# thermo_test.net
KiCad netlist of a schematic drawn in EAGLE
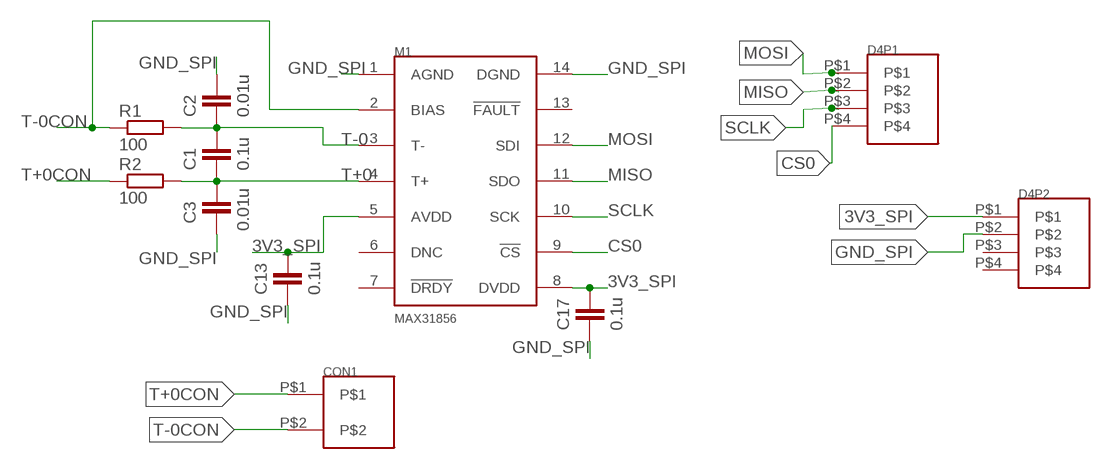
[diagram p0: schematic, sheet 1]

(export (version "E")
  (design (tool "Eeschema 10.0.6"))
  (components
    (comp (ref "C1")
      (value "0.1u")
      (footprint "eagle-import:C0603")
      (libsource (lib "eagle-import") (part "C-EUC0603"))
    )
    (comp (ref "C2")
      (value "0.01u")
      (footprint "eagle-import:C0603")
      (libsource (lib "eagle-import") (part "C-EUC0603"))
    )
    (comp (ref "C3")
      (value "0.01u")
      (footprint "eagle-import:C0603")
      (libsource (lib "eagle-import") (part "C-EUC0603"))
    )
    (comp (ref "C13")
      (value "0.1u")
      (footprint "eagle-import:C0603")
      (libsource (lib "eagle-import") (part "C-EUC0603"))
    )
    (comp (ref "C17")
      (value "0.1u")
      (footprint "eagle-import:C0603")
      (libsource (lib "eagle-import") (part "C-EUC0603"))
    )
    (comp (ref "CON1")
      (value "893-1332")
      (footprint "eagle-import:893-1332")
      (libsource (lib "eagle-import") (part "893-1332"))
    )
    (comp (ref "D4P1")
      (value "DF1E-4P")
      (footprint "eagle-import:DF1E-4P")
      (libsource (lib "eagle-import") (part "DF1E-4P"))
    )
    (comp (ref "D4P2")
      (value "DF1E-4P")
      (footprint "eagle-import:DF1E-4P")
      (libsource (lib "eagle-import") (part "DF1E-4P"))
    )
    (comp (ref "M1")
      (value "MAX31856")
      (footprint "eagle-import:TSSOP14")
      (libsource (lib "eagle-import") (part "MAX31856"))
    )
    (comp (ref "R1")
      (value "100")
      (footprint "eagle-import:R0603")
      (libsource (lib "eagle-import") (part "R-EU_R0603"))
    )
    (comp (ref "R2")
      (value "100")
      (footprint "eagle-import:R0603")
      (libsource (lib "eagle-import") (part "R-EU_R0603"))
    )
  )
  (nets
    (net (code "1") (name "/T+0") (class "Default")
      (node (ref "C1") (pin "2") (pinfunction "2_2") (pintype "passive"))
      (node (ref "C3") (pin "1") (pinfunction "1_1") (pintype "passive"))
      (node (ref "M1") (pin "4") (pinfunction "T+_4") (pintype "bidirectional"))
      (node (ref "R2") (pin "2") (pinfunction "2_2") (pintype "passive"))
    )
    (net (code "2") (name "/T-0") (class "Default")
      (node (ref "C1") (pin "1") (pinfunction "1_1") (pintype "passive"))
      (node (ref "C2") (pin "2") (pinfunction "2_2") (pintype "passive"))
      (node (ref "M1") (pin "3") (pinfunction "T-_3") (pintype "bidirectional"))
      (node (ref "R1") (pin "2") (pinfunction "2_2") (pintype "passive"))
    )
    (net (code "3") (name "3V3_SPI") (class "Default")
      (node (ref "C13") (pin "1") (pinfunction "1_1") (pintype "passive"))
      (node (ref "C17") (pin "1") (pinfunction "1_1") (pintype "passive"))
      (node (ref "D4P2") (pin "P$1") (pinfunction "P$1_P$1") (pintype "bidirectional"))
      (node (ref "M1") (pin "5") (pinfunction "AVDD_5") (pintype "bidirectional"))
      (node (ref "M1") (pin "8") (pinfunction "DVDD_8") (pintype "bidirectional"))
    )
    (net (code "4") (name "CS0") (class "Default")
      (node (ref "D4P1") (pin "P$4") (pinfunction "P$4_P$4") (pintype "bidirectional"))
      (node (ref "M1") (pin "9") (pinfunction "~{CS}_9") (pintype "bidirectional"))
    )
    (net (code "5") (name "GND_SPI") (class "Default")
      (node (ref "C13") (pin "2") (pinfunction "2_2") (pintype "passive"))
      (node (ref "C17") (pin "2") (pinfunction "2_2") (pintype "passive"))
      (node (ref "C2") (pin "1") (pinfunction "1_1") (pintype "passive"))
      (node (ref "C3") (pin "2") (pinfunction "2_2") (pintype "passive"))
      (node (ref "D4P2") (pin "P$2") (pinfunction "P$2_P$2") (pintype "bidirectional"))
      (node (ref "M1") (pin "1") (pinfunction "AGND_1") (pintype "bidirectional"))
      (node (ref "M1") (pin "14") (pinfunction "DGND_14") (pintype "bidirectional"))
    )
    (net (code "6") (name "MISO") (class "Default")
      (node (ref "D4P1") (pin "P$2") (pinfunction "P$2_P$2") (pintype "bidirectional"))
      (node (ref "M1") (pin "11") (pinfunction "SDO_11") (pintype "bidirectional"))
    )
    (net (code "7") (name "MOSI") (class "Default")
      (node (ref "D4P1") (pin "P$1") (pinfunction "P$1_P$1") (pintype "bidirectional"))
      (node (ref "M1") (pin "12") (pinfunction "SDI_12") (pintype "bidirectional"))
    )
    (net (code "8") (name "SCLK") (class "Default")
      (node (ref "D4P1") (pin "P$3") (pinfunction "P$3_P$3") (pintype "bidirectional"))
      (node (ref "M1") (pin "10") (pinfunction "SCK_10") (pintype "bidirectional"))
    )
    (net (code "9") (name "T+0CON") (class "Default")
      (node (ref "CON1") (pin "P$1") (pinfunction "P$1_P$1") (pintype "bidirectional"))
      (node (ref "R2") (pin "1") (pinfunction "1_1") (pintype "passive"))
    )
    (net (code "10") (name "T-0CON") (class "Default")
      (node (ref "CON1") (pin "P$2") (pinfunction "P$2_P$2") (pintype "bidirectional"))
      (node (ref "M1") (pin "2") (pinfunction "BIAS_2") (pintype "bidirectional"))
      (node (ref "R1") (pin "1") (pinfunction "1_1") (pintype "passive"))
    )
    (net (code "11") (name "unconnected-(D4P2-PadP$3)") (class "Default")
      (node (ref "D4P2") (pin "P$3") (pinfunction "P$3_P$3") (pintype "bidirectional"))
    )
    (net (code "12") (name "unconnected-(D4P2-PadP$4)") (class "Default")
      (node (ref "D4P2") (pin "P$4") (pinfunction "P$4_P$4") (pintype "bidirectional"))
    )
    (net (code "13") (name "unconnected-(M1-DNC-Pad6)") (class "Default")
      (node (ref "M1") (pin "6") (pinfunction "DNC_6") (pintype "bidirectional"))
    )
    (net (code "14") (name "unconnected-(M1-~{DRDY}-Pad7)") (class "Default")
      (node (ref "M1") (pin "7") (pinfunction "~{DRDY}_7") (pintype "bidirectional"))
    )
    (net (code "15") (name "unconnected-(M1-~{FAULT}-Pad13)") (class "Default")
      (node (ref "M1") (pin "13") (pinfunction "~{FAULT}_13") (pintype "bidirectional"))
    )
  )
)
